# THAT4305_Comp.net
KiCad netlist of a schematic drawn in EAGLE
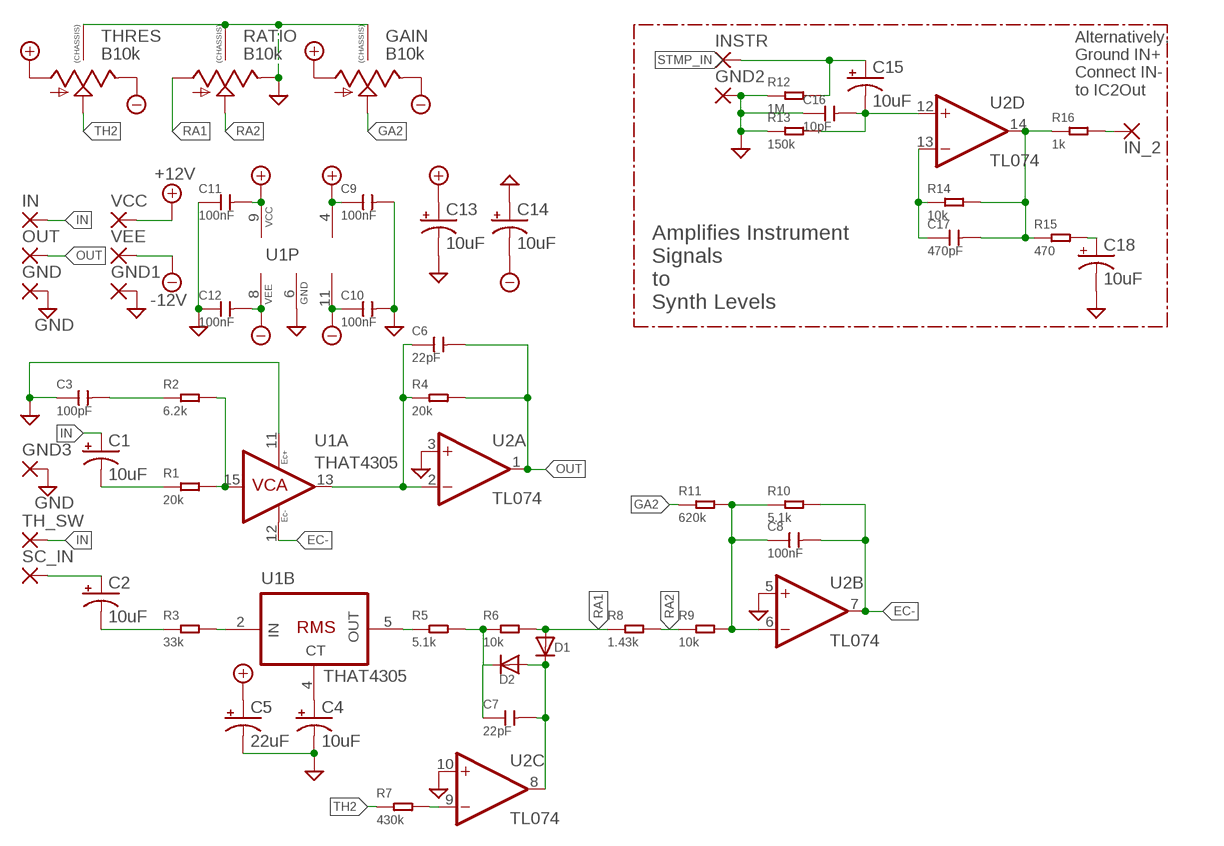
[diagram p0: schematic, sheet 1]

(export (version "E")
  (design (tool "Eeschema 10.0.6"))
  (components
    (comp (ref "C1")
      (value "10uF")
      (footprint "eagle-import:PAN_B_SMD+THRU")
      (libsource (lib "eagle-import") (part "CAP_SMD+THRUPAN_B"))
    )
    (comp (ref "C2")
      (value "10uF")
      (footprint "eagle-import:PAN_B_SMD+THRU")
      (libsource (lib "eagle-import") (part "CAP_SMD+THRUPAN_B"))
    )
    (comp (ref "C3")
      (value "100pF")
      (footprint "eagle-import:C0805")
      (fields (field (name "MPN") "CC0805KKX7R8BB105"))
      (libsource (lib "eagle-import") (part "CERAMIC-1UF-25V-10%-X7R(0805)"))
    )
    (comp (ref "C4")
      (value "10uF")
      (footprint "eagle-import:PAN_B_SMD+THRU")
      (libsource (lib "eagle-import") (part "CAP_SMD+THRUPAN_B"))
    )
    (comp (ref "C5")
      (value "22uF")
      (footprint "eagle-import:PAN_B_SMD+THRU")
      (libsource (lib "eagle-import") (part "CAP_SMD+THRUPAN_B"))
    )
    (comp (ref "C6")
      (value "22pF")
      (footprint "eagle-import:C0805")
      (fields (field (name "MPN") "CC0805KKX7R8BB105"))
      (libsource (lib "eagle-import") (part "CERAMIC-1UF-25V-10%-X7R(0805)"))
    )
    (comp (ref "C7")
      (value "22pF")
      (footprint "eagle-import:C0805")
      (fields (field (name "MPN") "CC0805KKX7R8BB105"))
      (libsource (lib "eagle-import") (part "CERAMIC-1UF-25V-10%-X7R(0805)"))
    )
    (comp (ref "C8")
      (value "100nF")
      (footprint "eagle-import:C0805")
      (fields (field (name "MPN") "CC0805KKX7R8BB105"))
      (libsource (lib "eagle-import") (part "CERAMIC-1UF-25V-10%-X7R(0805)"))
    )
    (comp (ref "C9")
      (value "100nF")
      (footprint "eagle-import:C0805")
      (fields (field (name "MPN") "CC0805KKX7R8BB105"))
      (libsource (lib "eagle-import") (part "CERAMIC-1UF-25V-10%-X7R(0805)"))
    )
    (comp (ref "C10")
      (value "100nF")
      (footprint "eagle-import:C0805")
      (fields (field (name "MPN") "CC0805KKX7R8BB105"))
      (libsource (lib "eagle-import") (part "CERAMIC-1UF-25V-10%-X7R(0805)"))
    )
    (comp (ref "C11")
      (value "100nF")
      (footprint "eagle-import:C0805")
      (fields (field (name "MPN") "CC0805KKX7R8BB105"))
      (libsource (lib "eagle-import") (part "CERAMIC-1UF-25V-10%-X7R(0805)"))
    )
    (comp (ref "C12")
      (value "100nF")
      (footprint "eagle-import:C0805")
      (fields (field (name "MPN") "CC0805KKX7R8BB105"))
      (libsource (lib "eagle-import") (part "CERAMIC-1UF-25V-10%-X7R(0805)"))
    )
    (comp (ref "C13")
      (value "10uF")
      (footprint "eagle-import:PAN_B_SMD+THRU")
      (libsource (lib "eagle-import") (part "CAP_SMD+THRUPAN_B"))
    )
    (comp (ref "C14")
      (value "10uF")
      (footprint "eagle-import:PAN_B_SMD+THRU")
      (libsource (lib "eagle-import") (part "CAP_SMD+THRUPAN_B"))
    )
    (comp (ref "C15")
      (value "10uF")
      (footprint "eagle-import:PAN_B_SMD+THRU")
      (libsource (lib "eagle-import") (part "CAP_SMD+THRUPAN_B"))
    )
    (comp (ref "C16")
      (value "10pF")
      (footprint "eagle-import:C0805")
      (fields (field (name "MPN") "CC0805KKX7R8BB105"))
      (libsource (lib "eagle-import") (part "CERAMIC-1UF-25V-10%-X7R(0805)"))
    )
    (comp (ref "C17")
      (value "470pF")
      (footprint "eagle-import:C0805")
      (fields (field (name "MPN") "CC0805KKX7R8BB105"))
      (libsource (lib "eagle-import") (part "CERAMIC-1UF-25V-10%-X7R(0805)"))
    )
    (comp (ref "C18")
      (value "10uF")
      (footprint "eagle-import:PAN_B_SMD+THRU")
      (libsource (lib "eagle-import") (part "CAP_SMD+THRUPAN_B"))
    )
    (comp (ref "D1")
      (value "DIODESOD-123")
      (footprint "eagle-import:SOD-123")
      (libsource (lib "eagle-import") (part "DIODESOD-123"))
    )
    (comp (ref "D2")
      (value "DIODESOD-123")
      (footprint "eagle-import:SOD-123")
      (libsource (lib "eagle-import") (part "DIODESOD-123"))
    )
    (comp (ref "GAIN")
      (value "B10k")
      (footprint "eagle-import:9MM_SNAP-IN_POT")
      (libsource (lib "eagle-import") (part "9MM_SNAP-IN_POT_CHASSIS"))
    )
    (comp (ref "GND")
      (value "WIREPAD1,6/0,9")
      (footprint "eagle-import:1,6_0,9")
      (libsource (lib "eagle-import") (part "WIREPAD1,6/0,9"))
    )
    (comp (ref "GND1")
      (value "WIREPAD1,6/0,9")
      (footprint "eagle-import:1,6_0,9")
      (libsource (lib "eagle-import") (part "WIREPAD1,6/0,9"))
    )
    (comp (ref "GND2")
      (value "WIREPAD1,6/0,9")
      (footprint "eagle-import:1,6_0,9")
      (libsource (lib "eagle-import") (part "WIREPAD1,6/0,9"))
    )
    (comp (ref "GND3")
      (value "WIREPAD1,6/0,9")
      (footprint "eagle-import:1,6_0,9")
      (libsource (lib "eagle-import") (part "WIREPAD1,6/0,9"))
    )
    (comp (ref "IN")
      (value "WIREPAD1,6/0,9")
      (footprint "eagle-import:1,6_0,9")
      (libsource (lib "eagle-import") (part "WIREPAD1,6/0,9"))
    )
    (comp (ref "INSTR")
      (value "WIREPAD1,6/0,9")
      (footprint "eagle-import:1,6_0,9")
      (libsource (lib "eagle-import") (part "WIREPAD1,6/0,9"))
    )
    (comp (ref "IN_2")
      (value "WIREPAD1,6/0,9")
      (footprint "eagle-import:1,6_0,9")
      (libsource (lib "eagle-import") (part "WIREPAD1,6/0,9"))
    )
    (comp (ref "OUT")
      (value "WIREPAD1,6/0,9")
      (footprint "eagle-import:1,6_0,9")
      (libsource (lib "eagle-import") (part "WIREPAD1,6/0,9"))
    )
    (comp (ref "R1")
      (value "20k")
      (footprint "eagle-import:R0805")
      (fields (field (name "MPN") "RC0805JR-071KL"))
      (libsource (lib "eagle-import") (part "SMD-RES-20K-5%-1/8W(0805)"))
    )
    (comp (ref "R2")
      (value "6.2k")
      (footprint "eagle-import:R0805")
      (fields (field (name "MPN") "RC0805JR-071KL"))
      (libsource (lib "eagle-import") (part "SMD-RES-20K-5%-1/8W(0805)"))
    )
    (comp (ref "R3")
      (value "33k")
      (footprint "eagle-import:R0805")
      (fields (field (name "MPN") "RC0805JR-071KL"))
      (libsource (lib "eagle-import") (part "SMD-RES-20K-5%-1/8W(0805)"))
    )
    (comp (ref "R4")
      (value "20k")
      (footprint "eagle-import:R0805")
      (fields (field (name "MPN") "RC0805JR-071KL"))
      (libsource (lib "eagle-import") (part "SMD-RES-20K-5%-1/8W(0805)"))
    )
    (comp (ref "R5")
      (value "5.1k")
      (footprint "eagle-import:R0805")
      (fields (field (name "MPN") "RC0805JR-071KL"))
      (libsource (lib "eagle-import") (part "SMD-RES-20K-5%-1/8W(0805)"))
    )
    (comp (ref "R6")
      (value "10k")
      (footprint "eagle-import:R0805")
      (fields (field (name "MPN") "RC0805JR-071KL"))
      (libsource (lib "eagle-import") (part "SMD-RES-20K-5%-1/8W(0805)"))
    )
    (comp (ref "R7")
      (value "430k")
      (footprint "eagle-import:R0805")
      (fields (field (name "MPN") "RC0805JR-071KL"))
      (libsource (lib "eagle-import") (part "SMD-RES-20K-5%-1/8W(0805)"))
    )
    (comp (ref "R8")
      (value "1.43k")
      (footprint "eagle-import:R0805")
      (fields (field (name "MPN") "RC0805JR-071KL"))
      (libsource (lib "eagle-import") (part "SMD-RES-20K-5%-1/8W(0805)"))
    )
    (comp (ref "R9")
      (value "10k")
      (footprint "eagle-import:R0805")
      (fields (field (name "MPN") "RC0805JR-071KL"))
      (libsource (lib "eagle-import") (part "SMD-RES-20K-5%-1/8W(0805)"))
    )
    (comp (ref "R10")
      (value "5.1k")
      (footprint "eagle-import:R0805")
      (fields (field (name "MPN") "RC0805JR-071KL"))
      (libsource (lib "eagle-import") (part "SMD-RES-20K-5%-1/8W(0805)"))
    )
    (comp (ref "R11")
      (value "620k")
      (footprint "eagle-import:R0805")
      (fields (field (name "MPN") "RC0805JR-071KL"))
      (libsource (lib "eagle-import") (part "SMD-RES-20K-5%-1/8W(0805)"))
    )
    (comp (ref "R12")
      (value "1M")
      (footprint "eagle-import:R0805")
      (fields (field (name "MPN") "RC0805JR-071KL"))
      (libsource (lib "eagle-import") (part "SMD-RES-20K-5%-1/8W(0805)"))
    )
    (comp (ref "R13")
      (value "150k")
      (footprint "eagle-import:R0805")
      (fields (field (name "MPN") "RC0805JR-071KL"))
      (libsource (lib "eagle-import") (part "SMD-RES-20K-5%-1/8W(0805)"))
    )
    (comp (ref "R14")
      (value "10k")
      (footprint "eagle-import:R0805")
      (fields (field (name "MPN") "RC0805JR-071KL"))
      (libsource (lib "eagle-import") (part "SMD-RES-20K-5%-1/8W(0805)"))
    )
    (comp (ref "R15")
      (value "470")
      (footprint "eagle-import:R0805")
      (fields (field (name "MPN") "RC0805JR-071KL"))
      (libsource (lib "eagle-import") (part "SMD-RES-20K-5%-1/8W(0805)"))
    )
    (comp (ref "R16")
      (value "1k")
      (footprint "eagle-import:R0805")
      (fields (field (name "MPN") "RC0805JR-071KL"))
      (libsource (lib "eagle-import") (part "SMD-RES-20K-5%-1/8W(0805)"))
    )
    (comp (ref "RATIO")
      (value "B10k")
      (footprint "eagle-import:9MM_SNAP-IN_POT")
      (libsource (lib "eagle-import") (part "9MM_SNAP-IN_POT_CHASSIS"))
    )
    (comp (ref "SC_IN")
      (value "WIREPAD1,6/0,9")
      (footprint "eagle-import:1,6_0,9")
      (libsource (lib "eagle-import") (part "WIREPAD1,6/0,9"))
    )
    (comp (ref "THRES")
      (value "B10k")
      (footprint "eagle-import:9MM_SNAP-IN_POT")
      (libsource (lib "eagle-import") (part "9MM_SNAP-IN_POT_CHASSIS"))
    )
    (comp (ref "TH_SW")
      (value "WIREPAD1,6/0,9")
      (footprint "eagle-import:1,6_0,9")
      (libsource (lib "eagle-import") (part "WIREPAD1,6/0,9"))
    )
    (comp (ref "U1")
      (value "THAT4305")
      (footprint "eagle-import:QSOP16")
      (libsource (lib "eagle-import") (part "THAT4305Q16-U"))
    )
    (comp (ref "U2")
      (value "TL074")
      (footprint "eagle-import:SO14")
      (libsource (lib "eagle-import") (part "TL074_SMD"))
    )
    (comp (ref "VCC")
      (value "WIREPAD1,6/0,9")
      (footprint "eagle-import:1,6_0,9")
      (libsource (lib "eagle-import") (part "WIREPAD1,6/0,9"))
    )
    (comp (ref "VEE")
      (value "WIREPAD1,6/0,9")
      (footprint "eagle-import:1,6_0,9")
      (libsource (lib "eagle-import") (part "WIREPAD1,6/0,9"))
    )
  )
  (nets
    (net (code "1") (name "+12V") (class "Default")
      (node (ref "C11") (pin "2") (pinfunction "2_2") (pintype "passive"))
      (node (ref "C13") (pin "+") (pinfunction "+_+") (pintype "passive"))
      (node (ref "C13") (pin "++") (pinfunction "+_++") (pintype "passive"))
      (node (ref "C5") (pin "+") (pinfunction "+_+") (pintype "passive"))
      (node (ref "C5") (pin "++") (pinfunction "+_++") (pintype "passive"))
      (node (ref "C9") (pin "1") (pinfunction "1_1") (pintype "passive"))
      (node (ref "GAIN") (pin "1") (pinfunction "A_1") (pintype "passive"))
      (node (ref "THRES") (pin "1") (pinfunction "A_1") (pintype "passive"))
      (node (ref "U1") (pin "9") (pinfunction "VCC_9") (pintype "power_in"))
      (node (ref "U2") (pin "4") (pinfunction "V+_4") (pintype "power_in"))
      (node (ref "VCC") (pin "1") (pinfunction "P_1") (pintype "passive"))
    )
    (net (code "2") (name "-12V") (class "Default")
      (node (ref "C10") (pin "1") (pinfunction "1_1") (pintype "passive"))
      (node (ref "C12") (pin "2") (pinfunction "2_2") (pintype "passive"))
      (node (ref "C14") (pin "-") (pinfunction "-_-") (pintype "passive"))
      (node (ref "C14") (pin "--") (pinfunction "-_--") (pintype "passive"))
      (node (ref "GAIN") (pin "3") (pinfunction "E_3") (pintype "passive"))
      (node (ref "THRES") (pin "3") (pinfunction "E_3") (pintype "passive"))
      (node (ref "U1") (pin "8") (pinfunction "VEE_8") (pintype "power_in"))
      (node (ref "U2") (pin "11") (pinfunction "V-_11") (pintype "power_in"))
      (node (ref "VEE") (pin "1") (pinfunction "P_1") (pintype "passive"))
    )
    (net (code "3") (name "EC-") (class "Default")
      (node (ref "C8") (pin "2") (pinfunction "2_2") (pintype "passive"))
      (node (ref "R10") (pin "2") (pinfunction "2_2") (pintype "passive"))
      (node (ref "U1") (pin "12") (pinfunction "EC-_12") (pintype "passive"))
      (node (ref "U2") (pin "7") (pinfunction "OUT_7") (pintype "output"))
    )
    (net (code "4") (name "GA2") (class "Default")
      (node (ref "GAIN") (pin "2") (pinfunction "S_2") (pintype "passive"))
      (node (ref "R11") (pin "1") (pinfunction "1_1") (pintype "passive"))
    )
    (net (code "5") (name "GND") (class "Default")
      (node (ref "C10") (pin "2") (pinfunction "2_2") (pintype "passive"))
      (node (ref "C11") (pin "1") (pinfunction "1_1") (pintype "passive"))
      (node (ref "C12") (pin "1") (pinfunction "1_1") (pintype "passive"))
      (node (ref "C13") (pin "-") (pinfunction "-_-") (pintype "passive"))
      (node (ref "C13") (pin "--") (pinfunction "-_--") (pintype "passive"))
      (node (ref "C14") (pin "+") (pinfunction "+_+") (pintype "passive"))
      (node (ref "C14") (pin "++") (pinfunction "+_++") (pintype "passive"))
      (node (ref "C16") (pin "1") (pinfunction "1_1") (pintype "passive"))
      (node (ref "C18") (pin "-") (pinfunction "-_-") (pintype "passive"))
      (node (ref "C18") (pin "--") (pinfunction "-_--") (pintype "passive"))
      (node (ref "C3") (pin "1") (pinfunction "1_1") (pintype "passive"))
      (node (ref "C4") (pin "-") (pinfunction "-_-") (pintype "passive"))
      (node (ref "C4") (pin "--") (pinfunction "-_--") (pintype "passive"))
      (node (ref "C5") (pin "-") (pinfunction "-_-") (pintype "passive"))
      (node (ref "C5") (pin "--") (pinfunction "-_--") (pintype "passive"))
      (node (ref "C9") (pin "2") (pinfunction "2_2") (pintype "passive"))
      (node (ref "GAIN") (pin "CHASSIS1") (pinfunction "P$1_CHASSIS1") (pintype "passive"))
      (node (ref "GAIN") (pin "CHASSIS2") (pinfunction "P$1_CHASSIS2") (pintype "passive"))
      (node (ref "GND") (pin "1") (pinfunction "P_1") (pintype "passive"))
      (node (ref "GND1") (pin "1") (pinfunction "P_1") (pintype "passive"))
      (node (ref "GND2") (pin "1") (pinfunction "P_1") (pintype "passive"))
      (node (ref "GND3") (pin "1") (pinfunction "P_1") (pintype "passive"))
      (node (ref "R12") (pin "1") (pinfunction "1_1") (pintype "passive"))
      (node (ref "R13") (pin "1") (pinfunction "1_1") (pintype "passive"))
      (node (ref "RATIO") (pin "3") (pinfunction "E_3") (pintype "passive"))
      (node (ref "RATIO") (pin "CHASSIS1") (pinfunction "P$1_CHASSIS1") (pintype "passive"))
      (node (ref "RATIO") (pin "CHASSIS2") (pinfunction "P$1_CHASSIS2") (pintype "passive"))
      (node (ref "THRES") (pin "CHASSIS1") (pinfunction "P$1_CHASSIS1") (pintype "passive"))
      (node (ref "THRES") (pin "CHASSIS2") (pinfunction "P$1_CHASSIS2") (pintype "passive"))
      (node (ref "U1") (pin "11") (pinfunction "EC+_11") (pintype "passive"))
      (node (ref "U1") (pin "6") (pinfunction "GND_6") (pintype "power_in"))
      (node (ref "U2") (pin "10") (pinfunction "+IN_10") (pintype "input"))
      (node (ref "U2") (pin "3") (pinfunction "+IN_3") (pintype "input"))
      (node (ref "U2") (pin "5") (pinfunction "+IN_5") (pintype "input"))
    )
    (net (code "6") (name "IN") (class "Default")
      (node (ref "C1") (pin "+") (pinfunction "+_+") (pintype "passive"))
      (node (ref "C1") (pin "++") (pinfunction "+_++") (pintype "passive"))
      (node (ref "IN") (pin "1") (pinfunction "P_1") (pintype "passive"))
      (node (ref "TH_SW") (pin "1") (pinfunction "P_1") (pintype "passive"))
    )
    (net (code "7") (name "Net-(C1---Pad--)") (class "Default")
      (node (ref "C1") (pin "-") (pinfunction "-_-") (pintype "passive"))
      (node (ref "C1") (pin "--") (pinfunction "-_--") (pintype "passive"))
      (node (ref "R1") (pin "1") (pinfunction "1_1") (pintype "passive"))
    )
    (net (code "8") (name "Net-(C2---Pad--)") (class "Default")
      (node (ref "C2") (pin "-") (pinfunction "-_-") (pintype "passive"))
      (node (ref "C2") (pin "--") (pinfunction "-_--") (pintype "passive"))
      (node (ref "R3") (pin "1") (pinfunction "1_1") (pintype "passive"))
    )
    (net (code "9") (name "Net-(C3-Pad2)") (class "Default")
      (node (ref "C3") (pin "2") (pinfunction "2_2") (pintype "passive"))
      (node (ref "R2") (pin "1") (pinfunction "1_1") (pintype "passive"))
    )
    (net (code "10") (name "Net-(C7-Pad1)") (class "Default")
      (node (ref "C7") (pin "1") (pinfunction "1_1") (pintype "passive"))
      (node (ref "D2") (pin "C") (pinfunction "C_C") (pintype "passive"))
      (node (ref "R5") (pin "2") (pinfunction "2_2") (pintype "passive"))
      (node (ref "R6") (pin "1") (pinfunction "1_1") (pintype "passive"))
    )
    (net (code "11") (name "Net-(C18-+-Pad++)") (class "Default")
      (node (ref "C18") (pin "+") (pinfunction "+_+") (pintype "passive"))
      (node (ref "C18") (pin "++") (pinfunction "+_++") (pintype "passive"))
      (node (ref "R15") (pin "2") (pinfunction "2_2") (pintype "passive"))
    )
    (net (code "12") (name "Net-(IN_2-P)") (class "Default")
      (node (ref "IN_2") (pin "1") (pinfunction "P_1") (pintype "passive"))
      (node (ref "R16") (pin "2") (pinfunction "2_2") (pintype "passive"))
    )
    (net (code "13") (name "Net-(SC_IN-P)") (class "Default")
      (node (ref "C2") (pin "+") (pinfunction "+_+") (pintype "passive"))
      (node (ref "C2") (pin "++") (pinfunction "+_++") (pintype "passive"))
      (node (ref "SC_IN") (pin "1") (pinfunction "P_1") (pintype "passive"))
    )
    (net (code "14") (name "Net-(U1A-VCA_IN)") (class "Default")
      (node (ref "R1") (pin "2") (pinfunction "2_2") (pintype "passive"))
      (node (ref "R2") (pin "2") (pinfunction "2_2") (pintype "passive"))
      (node (ref "U1") (pin "15") (pinfunction "VCA_IN_15") (pintype "input"))
    )
    (net (code "15") (name "Net-(U1A-VCA_OUT)") (class "Default")
      (node (ref "C6") (pin "1") (pinfunction "1_1") (pintype "passive"))
      (node (ref "R4") (pin "1") (pinfunction "1_1") (pintype "passive"))
      (node (ref "U1") (pin "13") (pinfunction "VCA_OUT_13") (pintype "output"))
      (node (ref "U2") (pin "2") (pinfunction "-IN_2") (pintype "input"))
    )
    (net (code "16") (name "Net-(U1B-CT)") (class "Default")
      (node (ref "C4") (pin "+") (pinfunction "+_+") (pintype "passive"))
      (node (ref "C4") (pin "++") (pinfunction "+_++") (pintype "passive"))
      (node (ref "U1") (pin "4") (pinfunction "CT_4") (pintype "passive"))
    )
    (net (code "17") (name "Net-(U1B-RMS_IN)") (class "Default")
      (node (ref "R3") (pin "2") (pinfunction "2_2") (pintype "passive"))
      (node (ref "U1") (pin "2") (pinfunction "RMS_IN_2") (pintype "input"))
    )
    (net (code "18") (name "Net-(U1B-RMS_OUT)") (class "Default")
      (node (ref "R5") (pin "1") (pinfunction "1_1") (pintype "passive"))
      (node (ref "U1") (pin "5") (pinfunction "RMS_OUT_5") (pintype "output"))
    )
    (net (code "19") (name "Net-(U2B--IN)") (class "Default")
      (node (ref "C8") (pin "1") (pinfunction "1_1") (pintype "passive"))
      (node (ref "R10") (pin "1") (pinfunction "1_1") (pintype "passive"))
      (node (ref "R11") (pin "2") (pinfunction "2_2") (pintype "passive"))
      (node (ref "R9") (pin "2") (pinfunction "2_2") (pintype "passive"))
      (node (ref "U2") (pin "6") (pinfunction "-IN_6") (pintype "input"))
    )
    (net (code "20") (name "Net-(U2C--IN)") (class "Default")
      (node (ref "R7") (pin "2") (pinfunction "2_2") (pintype "passive"))
      (node (ref "U2") (pin "9") (pinfunction "-IN_9") (pintype "input"))
    )
    (net (code "21") (name "Net-(U2C-OUT)") (class "Default")
      (node (ref "C7") (pin "2") (pinfunction "2_2") (pintype "passive"))
      (node (ref "D1") (pin "C") (pinfunction "C_C") (pintype "passive"))
      (node (ref "D2") (pin "A") (pinfunction "A_A") (pintype "passive"))
      (node (ref "U2") (pin "8") (pinfunction "OUT_8") (pintype "output"))
    )
    (net (code "22") (name "Net-(U2D-+IN)") (class "Default")
      (node (ref "C15") (pin "-") (pinfunction "-_-") (pintype "passive"))
      (node (ref "C15") (pin "--") (pinfunction "-_--") (pintype "passive"))
      (node (ref "C16") (pin "2") (pinfunction "2_2") (pintype "passive"))
      (node (ref "R13") (pin "2") (pinfunction "2_2") (pintype "passive"))
      (node (ref "U2") (pin "12") (pinfunction "+IN_12") (pintype "input"))
    )
    (net (code "23") (name "Net-(U2D--IN)") (class "Default")
      (node (ref "C17") (pin "1") (pinfunction "1_1") (pintype "passive"))
      (node (ref "R14") (pin "1") (pinfunction "1_1") (pintype "passive"))
      (node (ref "U2") (pin "13") (pinfunction "-IN_13") (pintype "input"))
    )
    (net (code "24") (name "Net-(U2D-OUT)") (class "Default")
      (node (ref "C17") (pin "2") (pinfunction "2_2") (pintype "passive"))
      (node (ref "R14") (pin "2") (pinfunction "2_2") (pintype "passive"))
      (node (ref "R15") (pin "1") (pinfunction "1_1") (pintype "passive"))
      (node (ref "R16") (pin "1") (pinfunction "1_1") (pintype "passive"))
      (node (ref "U2") (pin "14") (pinfunction "OUT_14") (pintype "output"))
    )
    (net (code "25") (name "OUT") (class "Default")
      (node (ref "C6") (pin "2") (pinfunction "2_2") (pintype "passive"))
      (node (ref "OUT") (pin "1") (pinfunction "P_1") (pintype "passive"))
      (node (ref "R4") (pin "2") (pinfunction "2_2") (pintype "passive"))
      (node (ref "U2") (pin "1") (pinfunction "OUT_1") (pintype "output"))
    )
    (net (code "26") (name "RA1") (class "Default")
      (node (ref "D1") (pin "A") (pinfunction "A_A") (pintype "passive"))
      (node (ref "R6") (pin "2") (pinfunction "2_2") (pintype "passive"))
      (node (ref "R8") (pin "1") (pinfunction "1_1") (pintype "passive"))
      (node (ref "RATIO") (pin "1") (pinfunction "A_1") (pintype "passive"))
    )
    (net (code "27") (name "RA2") (class "Default")
      (node (ref "R8") (pin "2") (pinfunction "2_2") (pintype "passive"))
      (node (ref "R9") (pin "1") (pinfunction "1_1") (pintype "passive"))
      (node (ref "RATIO") (pin "2") (pinfunction "S_2") (pintype "passive"))
    )
    (net (code "28") (name "STMP_IN") (class "Default")
      (node (ref "C15") (pin "+") (pinfunction "+_+") (pintype "passive"))
      (node (ref "C15") (pin "++") (pinfunction "+_++") (pintype "passive"))
      (node (ref "INSTR") (pin "1") (pinfunction "P_1") (pintype "passive"))
      (node (ref "R12") (pin "2") (pinfunction "2_2") (pintype "passive"))
    )
    (net (code "29") (name "TH2") (class "Default")
      (node (ref "R7") (pin "1") (pinfunction "1_1") (pintype "passive"))
      (node (ref "THRES") (pin "2") (pinfunction "S_2") (pintype "passive"))
    )
  )
)
